# LED_heart2.net
KiCad netlist of a schematic drawn in EAGLE
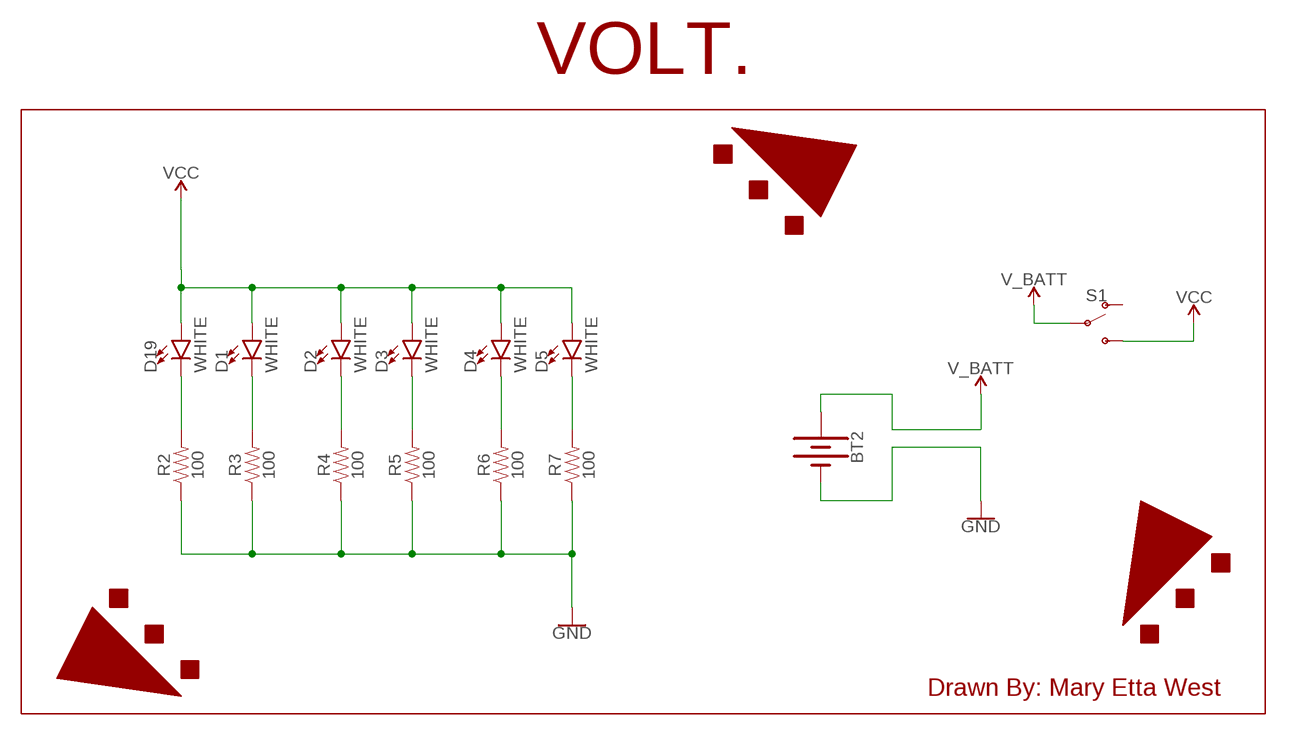
[diagram p0: schematic, sheet 1]

(export (version "E")
  (design (tool "Eeschema 10.0.6"))
  (components
    (comp (ref "BT2")
      (value "BATTERY-12MM_SMD")
      (footprint "eagle-import:BATTCON_12MM")
      (libsource (lib "eagle-import") (part "BATTERY-12MM_SMD"))
    )
    (comp (ref "D1")
      (value "WHITE")
      (footprint "eagle-import:LED-1206")
      (libsource (lib "eagle-import") (part "LED-WHITE1206"))
    )
    (comp (ref "D2")
      (value "WHITE")
      (footprint "eagle-import:LED-1206")
      (libsource (lib "eagle-import") (part "LED-WHITE1206"))
    )
    (comp (ref "D3")
      (value "WHITE")
      (footprint "eagle-import:LED-1206")
      (libsource (lib "eagle-import") (part "LED-WHITE1206"))
    )
    (comp (ref "D4")
      (value "WHITE")
      (footprint "eagle-import:LED-1206")
      (libsource (lib "eagle-import") (part "LED-WHITE1206"))
    )
    (comp (ref "D5")
      (value "WHITE")
      (footprint "eagle-import:LED-1206")
      (libsource (lib "eagle-import") (part "LED-WHITE1206"))
    )
    (comp (ref "D19")
      (value "WHITE")
      (footprint "eagle-import:LED-1206")
      (libsource (lib "eagle-import") (part "LED-WHITE1206"))
    )
    (comp (ref "R2")
      (value "100")
      (footprint "eagle-import:0603")
      (libsource (lib "eagle-import") (part "100OHM-0603-1/4W-5%"))
    )
    (comp (ref "R3")
      (value "100")
      (footprint "eagle-import:0603")
      (libsource (lib "eagle-import") (part "100OHM-0603-1/4W-5%"))
    )
    (comp (ref "R4")
      (value "100")
      (footprint "eagle-import:0603")
      (libsource (lib "eagle-import") (part "100OHM-0603-1/4W-5%"))
    )
    (comp (ref "R5")
      (value "100")
      (footprint "eagle-import:0603")
      (libsource (lib "eagle-import") (part "100OHM-0603-1/4W-5%"))
    )
    (comp (ref "R6")
      (value "100")
      (footprint "eagle-import:0603")
      (libsource (lib "eagle-import") (part "100OHM-0603-1/4W-5%"))
    )
    (comp (ref "R7")
      (value "100")
      (footprint "eagle-import:0603")
      (libsource (lib "eagle-import") (part "100OHM-0603-1/4W-5%"))
    )
    (comp (ref "S1")
      (value "SWITCH-SPDT-SMD-RIGHT-ANGLE")
      (footprint "eagle-import:SWITCH_SPST_SMD_A")
      (libsource (lib "eagle-import") (part "SWITCH-SPDT-SMD-RIGHT-ANGLE"))
    )
  )
  (nets
    (net (code "1") (name "GND") (class "Default")
      (node (ref "BT2") (pin "GND") (pinfunction "-_GND") (pintype "power_in"))
      (node (ref "R2") (pin "1") (pinfunction "1_1") (pintype "passive"))
      (node (ref "R3") (pin "1") (pinfunction "1_1") (pintype "passive"))
      (node (ref "R4") (pin "1") (pinfunction "1_1") (pintype "passive"))
      (node (ref "R5") (pin "1") (pinfunction "1_1") (pintype "passive"))
      (node (ref "R6") (pin "1") (pinfunction "1_1") (pintype "passive"))
      (node (ref "R7") (pin "1") (pinfunction "1_1") (pintype "passive"))
    )
    (net (code "2") (name "Net-(D1-PadC)") (class "Default")
      (node (ref "D1") (pin "C") (pinfunction "C_C") (pintype "passive"))
      (node (ref "R3") (pin "2") (pinfunction "2_2") (pintype "passive"))
    )
    (net (code "3") (name "Net-(D2-PadC)") (class "Default")
      (node (ref "D2") (pin "C") (pinfunction "C_C") (pintype "passive"))
      (node (ref "R4") (pin "2") (pinfunction "2_2") (pintype "passive"))
    )
    (net (code "4") (name "Net-(D3-PadC)") (class "Default")
      (node (ref "D3") (pin "C") (pinfunction "C_C") (pintype "passive"))
      (node (ref "R5") (pin "2") (pinfunction "2_2") (pintype "passive"))
    )
    (net (code "5") (name "Net-(D4-PadC)") (class "Default")
      (node (ref "D4") (pin "C") (pinfunction "C_C") (pintype "passive"))
      (node (ref "R6") (pin "2") (pinfunction "2_2") (pintype "passive"))
    )
    (net (code "6") (name "Net-(D5-PadC)") (class "Default")
      (node (ref "D5") (pin "C") (pinfunction "C_C") (pintype "passive"))
      (node (ref "R7") (pin "2") (pinfunction "2_2") (pintype "passive"))
    )
    (net (code "7") (name "Net-(D19-PadC)") (class "Default")
      (node (ref "D19") (pin "C") (pinfunction "C_C") (pintype "passive"))
      (node (ref "R2") (pin "2") (pinfunction "2_2") (pintype "passive"))
    )
    (net (code "8") (name "VCC") (class "Default")
      (node (ref "D1") (pin "A") (pinfunction "A_A") (pintype "passive"))
      (node (ref "D19") (pin "A") (pinfunction "A_A") (pintype "passive"))
      (node (ref "D2") (pin "A") (pinfunction "A_A") (pintype "passive"))
      (node (ref "D3") (pin "A") (pinfunction "A_A") (pintype "passive"))
      (node (ref "D4") (pin "A") (pinfunction "A_A") (pintype "passive"))
      (node (ref "D5") (pin "A") (pinfunction "A_A") (pintype "passive"))
      (node (ref "S1") (pin "3") (pinfunction "S_3") (pintype "passive"))
    )
    (net (code "9") (name "V_BATT") (class "Default")
      (node (ref "BT2") (pin "PWR@1") (pinfunction "+_PWR@1") (pintype "power_in"))
      (node (ref "S1") (pin "2") (pinfunction "P_2") (pintype "passive"))
    )
    (net (code "10") (name "unconnected-(S1-O-Pad1)") (class "Default")
      (node (ref "S1") (pin "1") (pinfunction "O_1") (pintype "passive"))
    )
  )
)
